# 3-Wire_ISCV_Driver.net
KiCad netlist of a schematic drawn in Altium Designer
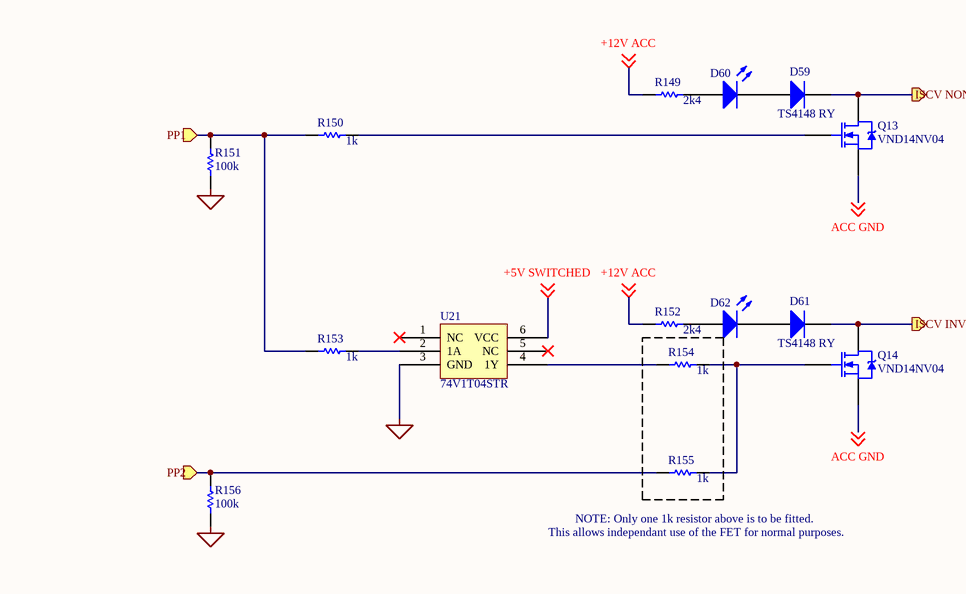
[diagram p0: 3-Wire ISCV Driver.SchDoc]

(export (version "E")
  (design (tool "Eeschema 10.0.6"))
  (components
    (comp (ref "D59")
      (value "TS4148 RY")
      (footprint "SMC")
      (description "Default Diode")
      (fields (field (name "PUBLISHER") "Altium Limited"))
      (libsource (lib "Miscellaneous Devices") (part "Diode"))
    )
    (comp (ref "D60")
      (value "~")
      (footprint "LED-0")
      (description "Typical INFRARED GaAs LED")
      (fields (field (name "PUBLISHER") "Altium Limited"))
      (libsource (lib "Miscellaneous Devices") (part "LED0"))
    )
    (comp (ref "D61")
      (value "TS4148 RY")
      (footprint "SMC")
      (description "Default Diode")
      (fields (field (name "PUBLISHER") "Altium Limited"))
      (libsource (lib "Miscellaneous Devices") (part "Diode"))
    )
    (comp (ref "D62")
      (value "~")
      (footprint "LED-0")
      (description "Typical INFRARED GaAs LED")
      (fields (field (name "PUBLISHER") "Altium Limited"))
      (libsource (lib "Miscellaneous Devices") (part "LED0"))
    )
    (comp (ref "Q13")
      (value "VND14NV04")
      (footprint "TO-220AB")
      (description "HEXFET Power MOSFET")
      (fields (field (name "PUBLISHER") "Altium Limited"))
      (libsource (lib "IR Discrete MOSFET - Power") (part "IRL520N"))
    )
    (comp (ref "Q14")
      (value "VND14NV04")
      (footprint "TO-220AB")
      (description "HEXFET Power MOSFET")
      (fields (field (name "PUBLISHER") "Altium Limited"))
      (libsource (lib "IR Discrete MOSFET - Power") (part "IRL520N"))
    )
    (comp (ref "R149")
      (value "2k4")
      (footprint "AXIAL-0.3")
      (description "Resistor")
      (fields (field (name "PUBLISHER") "Altium Limited"))
      (libsource (lib "Miscellaneous Devices") (part "Res1"))
    )
    (comp (ref "R150")
      (value "1k")
      (footprint "AXIAL-0.3")
      (description "Resistor")
      (fields (field (name "PUBLISHER") "Altium Limited"))
      (libsource (lib "Miscellaneous Devices") (part "Res1"))
    )
    (comp (ref "R151")
      (value "100k")
      (footprint "AXIAL-0.3")
      (description "Resistor")
      (fields (field (name "PUBLISHER") "Altium Limited"))
      (libsource (lib "Miscellaneous Devices") (part "Res1"))
    )
    (comp (ref "R152")
      (value "2k4")
      (footprint "AXIAL-0.3")
      (description "Resistor")
      (fields (field (name "PUBLISHER") "Altium Limited"))
      (libsource (lib "Miscellaneous Devices") (part "Res1"))
    )
    (comp (ref "R153")
      (value "1k")
      (footprint "AXIAL-0.3")
      (description "Resistor")
      (fields (field (name "PUBLISHER") "Altium Limited"))
      (libsource (lib "Miscellaneous Devices") (part "Res1"))
    )
    (comp (ref "R154")
      (value "1k")
      (footprint "AXIAL-0.3")
      (description "Resistor")
      (fields (field (name "PUBLISHER") "Altium Limited"))
      (libsource (lib "Miscellaneous Devices") (part "Res1"))
    )
    (comp (ref "R155")
      (value "1k")
      (footprint "AXIAL-0.3")
      (description "Resistor")
      (fields (field (name "PUBLISHER") "Altium Limited"))
      (libsource (lib "Miscellaneous Devices") (part "Res1"))
    )
    (comp (ref "R156")
      (value "100k")
      (footprint "AXIAL-0.3")
      (description "Resistor")
      (fields (field (name "PUBLISHER") "Altium Limited"))
      (libsource (lib "Miscellaneous Devices") (part "Res1"))
    )
    (comp (ref "U21") (value "74V1T04STR") (libsource (lib "FreeEMS Schematic Library") (part "74V1T04STR")))
  )
  (nets
    (net (code "1") (name "+5V SWITCHED") (class "Default")
      (node (ref "U21") (pin "6") (pinfunction "VCC_6") (pintype "passive"))
    )
    (net (code "2") (name "+12V ACC") (class "Default")
      (node (ref "R149") (pin "1") (pinfunction "1_1") (pintype "passive"))
      (node (ref "R152") (pin "1") (pinfunction "1_1") (pintype "passive"))
    )
    (net (code "3") (name "/ISCV INV") (class "Default")
      (node (ref "D61") (pin "2") (pinfunction "K_2") (pintype "passive"))
      (node (ref "Q14") (pin "2") (pinfunction "D_2") (pintype "passive"))
    )
    (net (code "4") (name "/ISCV NON-INV") (class "Default")
      (node (ref "D59") (pin "2") (pinfunction "K_2") (pintype "passive"))
      (node (ref "Q13") (pin "2") (pinfunction "D_2") (pintype "passive"))
    )
    (net (code "5") (name "/PP1") (class "Default")
      (node (ref "R150") (pin "1") (pinfunction "1_1") (pintype "passive"))
      (node (ref "R151") (pin "2") (pinfunction "2_2") (pintype "passive"))
      (node (ref "R153") (pin "1") (pinfunction "1_1") (pintype "passive"))
    )
    (net (code "6") (name "/PP2") (class "Default")
      (node (ref "R155") (pin "1") (pinfunction "1_1") (pintype "passive"))
      (node (ref "R156") (pin "2") (pinfunction "2_2") (pintype "passive"))
    )
    (net (code "7") (name "<NO NET>") (class "Default")
      (node (ref "R151") (pin "1") (pinfunction "1_1") (pintype "passive"))
      (node (ref "R156") (pin "1") (pinfunction "1_1") (pintype "passive"))
      (node (ref "U21") (pin "3") (pinfunction "GND_3") (pintype "passive"))
    )
    (net (code "8") (name "ACC GND") (class "Default")
      (node (ref "Q13") (pin "3") (pinfunction "S_3") (pintype "passive"))
      (node (ref "Q14") (pin "3") (pinfunction "S_3") (pintype "passive"))
    )
    (net (code "9") (name "Net-(D59-A)") (class "Default")
      (node (ref "D59") (pin "1") (pinfunction "A_1") (pintype "passive"))
      (node (ref "D60") (pin "2") (pinfunction "K_2") (pintype "passive"))
    )
    (net (code "10") (name "Net-(D60-A)") (class "Default")
      (node (ref "D60") (pin "1") (pinfunction "A_1") (pintype "passive"))
      (node (ref "R149") (pin "2") (pinfunction "2_2") (pintype "passive"))
    )
    (net (code "11") (name "Net-(D61-A)") (class "Default")
      (node (ref "D61") (pin "1") (pinfunction "A_1") (pintype "passive"))
      (node (ref "D62") (pin "2") (pinfunction "K_2") (pintype "passive"))
    )
    (net (code "12") (name "Net-(D62-A)") (class "Default")
      (node (ref "D62") (pin "1") (pinfunction "A_1") (pintype "passive"))
      (node (ref "R152") (pin "2") (pinfunction "2_2") (pintype "passive"))
    )
    (net (code "13") (name "Net-(Q13-G)") (class "Default")
      (node (ref "Q13") (pin "1") (pinfunction "G_1") (pintype "passive"))
      (node (ref "R150") (pin "2") (pinfunction "2_2") (pintype "passive"))
    )
    (net (code "14") (name "Net-(Q14-G)") (class "Default")
      (node (ref "Q14") (pin "1") (pinfunction "G_1") (pintype "passive"))
      (node (ref "R154") (pin "2") (pinfunction "2_2") (pintype "passive"))
      (node (ref "R155") (pin "2") (pinfunction "2_2") (pintype "passive"))
    )
    (net (code "15") (name "Net-(U21-1A)") (class "Default")
      (node (ref "R153") (pin "2") (pinfunction "2_2") (pintype "passive"))
      (node (ref "U21") (pin "2") (pinfunction "1A_2") (pintype "passive"))
    )
    (net (code "16") (name "Net-(U21-1Y)") (class "Default")
      (node (ref "R154") (pin "1") (pinfunction "1_1") (pintype "passive"))
      (node (ref "U21") (pin "4") (pinfunction "1Y_4") (pintype "passive"))
    )
    (net (code "17") (name "unconnected-(U21-NC-Pad1)") (class "Default")
      (node (ref "U21") (pin "1") (pinfunction "NC_1") (pintype "passive+no_connect"))
    )
    (net (code "18") (name "unconnected-(U21-NC-Pad5)") (class "Default")
      (node (ref "U21") (pin "5") (pinfunction "NC_5") (pintype "passive+no_connect"))
    )
  )
)
